# shifting_buttons.net
KiCad netlist of a schematic drawn in Altium Designer
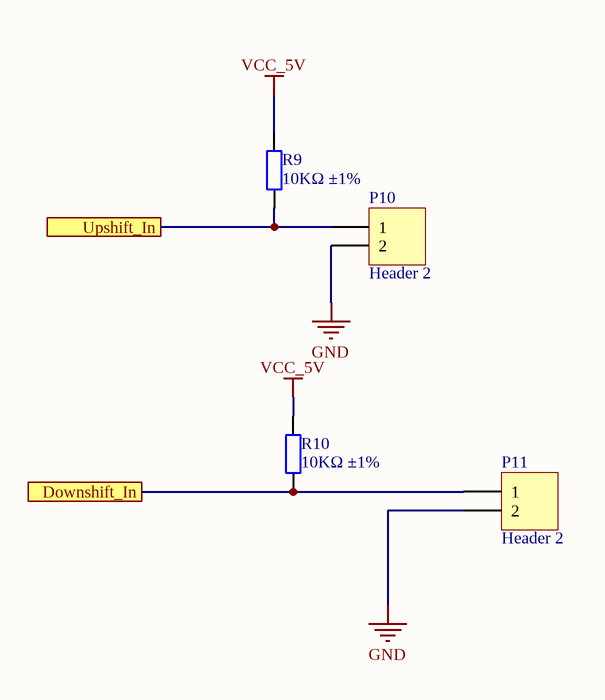
[diagram p0: shifting_buttons.SchDoc]

(export (version "E")
  (design (tool "Eeschema 10.0.6"))
  (components
    (comp (ref "P10")
      (value "Header 2")
      (footprint "HDR1X2")
      (description "Header, 2-Pin")
      (fields (field (name "PUBLISHER") "Altium Limited"))
      (libsource (lib "Miscellaneous Connectors") (part "Header 2"))
    )
    (comp (ref "P11")
      (value "Header 2")
      (footprint "HDR1X2")
      (description "Header, 2-Pin")
      (fields (field (name "PUBLISHER") "Altium Limited"))
      (libsource (lib "Miscellaneous Connectors") (part "Header 2"))
    )
    (comp (ref "R9")
      (value "10KΩ ±1%")
      (footprint "0603_R")
      (description "Chip resistor")
      (fields (field (name "MANUFACTURER") "Uniroyal Elec") (field (name "PARTNUMBER") "0603WAF1002T5E"))
      (libsource (lib "RES") (part "0603 10K (1002) 1%"))
    )
    (comp (ref "R10")
      (value "10KΩ ±1%")
      (footprint "0603_R")
      (description "Chip resistor")
      (fields (field (name "MANUFACTURER") "Uniroyal Elec") (field (name "PARTNUMBER") "0603WAF1002T5E"))
      (libsource (lib "RES") (part "0603 10K (1002) 1%"))
    )
  )
  (nets
    (net (code "1") (name "/Downshift_In") (class "Default")
      (node (ref "P11") (pin "1") (pinfunction "1_1") (pintype "passive"))
      (node (ref "R10") (pin "1") (pinfunction "1_1") (pintype "passive"))
    )
    (net (code "2") (name "/Upshift_In") (class "Default")
      (node (ref "P10") (pin "1") (pinfunction "1_1") (pintype "passive"))
      (node (ref "R9") (pin "1") (pinfunction "1_1") (pintype "passive"))
    )
    (net (code "3") (name "GND") (class "Default")
      (node (ref "P10") (pin "2") (pinfunction "2_2") (pintype "passive"))
      (node (ref "P11") (pin "2") (pinfunction "2_2") (pintype "passive"))
    )
    (net (code "4") (name "VCC_5V") (class "Default")
      (node (ref "R10") (pin "2") (pinfunction "2_2") (pintype "passive"))
      (node (ref "R9") (pin "2") (pinfunction "2_2") (pintype "passive"))
    )
  )
)
